# dtmf_rx.net
KiCad netlist of a schematic drawn in EAGLE
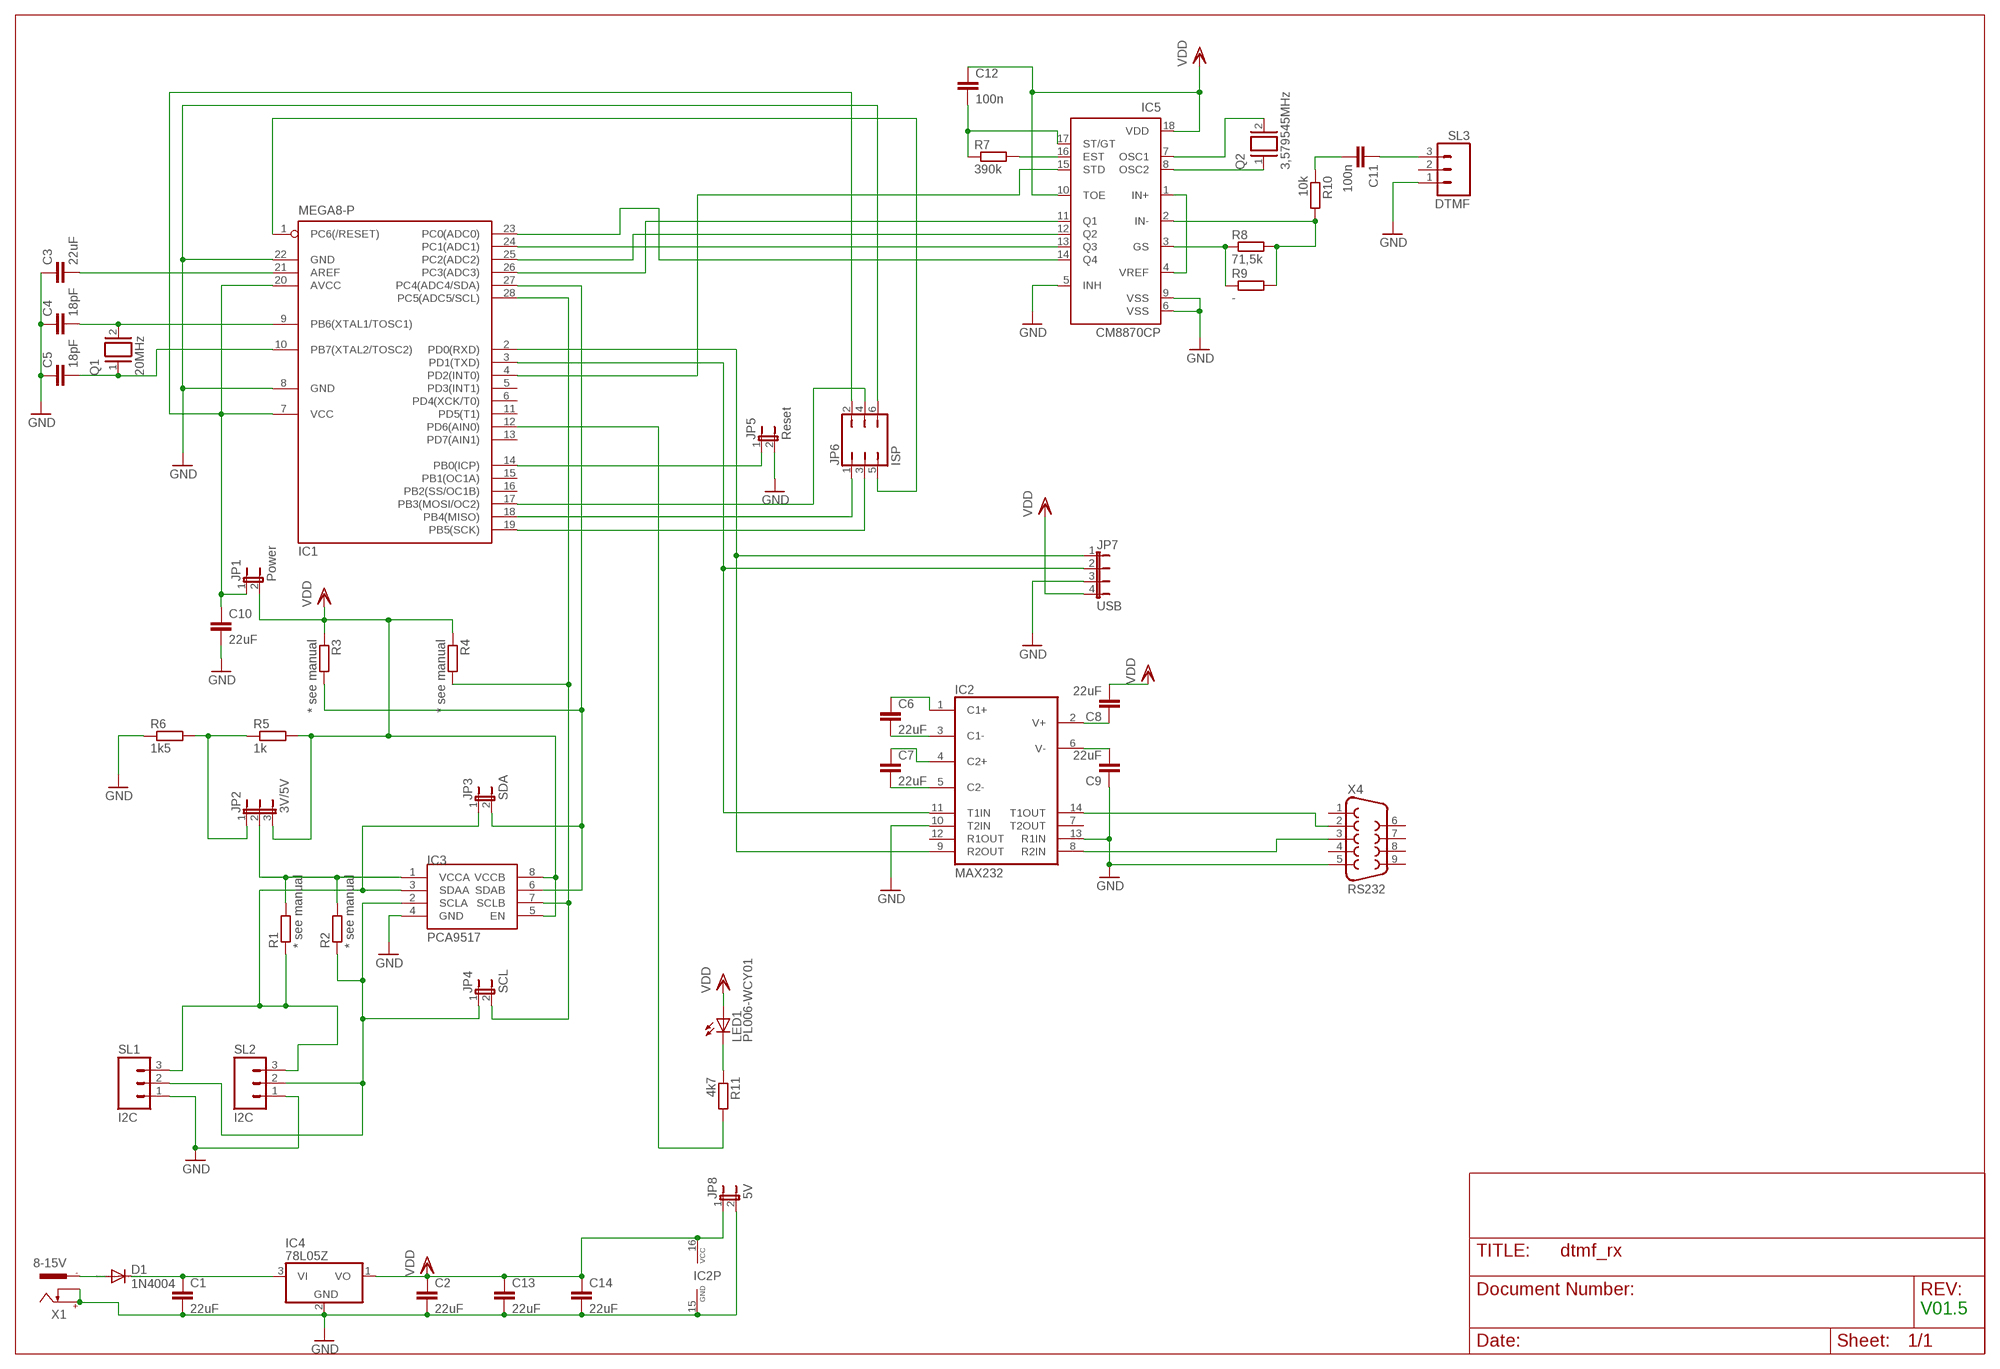
[diagram p0: schematic, sheet 1]

(export (version "E")
  (design (tool "Eeschema 10.0.6"))
  (components
    (comp (ref "C1")
      (value "22uF")
      (footprint "eagle-import:C1206")
      (libsource (lib "eagle-import") (part "C-EUC1206"))
    )
    (comp (ref "C2")
      (value "22uF")
      (footprint "eagle-import:C1206")
      (libsource (lib "eagle-import") (part "C-EUC1206"))
    )
    (comp (ref "C3")
      (value "22uF")
      (footprint "eagle-import:C1206")
      (libsource (lib "eagle-import") (part "C-EUC1206"))
    )
    (comp (ref "C4")
      (value "18pF")
      (footprint "eagle-import:C025-025X050")
      (libsource (lib "eagle-import") (part "resistor_C-EU025-025X050"))
    )
    (comp (ref "C5")
      (value "18pF")
      (footprint "eagle-import:C025-025X050")
      (libsource (lib "eagle-import") (part "resistor_C-EU025-025X050"))
    )
    (comp (ref "C6")
      (value "22uF")
      (footprint "eagle-import:C1206")
      (libsource (lib "eagle-import") (part "C-EUC1206"))
    )
    (comp (ref "C7")
      (value "22uF")
      (footprint "eagle-import:C1206")
      (libsource (lib "eagle-import") (part "C-EUC1206"))
    )
    (comp (ref "C8")
      (value "22uF")
      (footprint "eagle-import:C1206")
      (libsource (lib "eagle-import") (part "C-EUC1206"))
    )
    (comp (ref "C9")
      (value "22uF")
      (footprint "eagle-import:C1206")
      (libsource (lib "eagle-import") (part "C-EUC1206"))
    )
    (comp (ref "C10")
      (value "22uF")
      (footprint "eagle-import:C1206")
      (libsource (lib "eagle-import") (part "C-EUC1206"))
    )
    (comp (ref "C11")
      (value "100n")
      (footprint "eagle-import:C050-025X075")
      (libsource (lib "eagle-import") (part "C-EU050-025X075"))
    )
    (comp (ref "C12")
      (value "100n")
      (footprint "eagle-import:C050-025X075")
      (libsource (lib "eagle-import") (part "C-EU050-025X075"))
    )
    (comp (ref "C13")
      (value "22uF")
      (footprint "eagle-import:C1206")
      (libsource (lib "eagle-import") (part "C-EUC1206"))
    )
    (comp (ref "C14")
      (value "22uF")
      (footprint "eagle-import:C1206")
      (libsource (lib "eagle-import") (part "C-EUC1206"))
    )
    (comp (ref "D1")
      (value "1N4004")
      (footprint "eagle-import:DO41-10")
      (libsource (lib "eagle-import") (part "1N4004"))
    )
    (comp (ref "IC1")
      (value "MEGA8-P")
      (footprint "eagle-import:DIL28-3")
      (libsource (lib "eagle-import") (part "MEGA8-P"))
    )
    (comp (ref "IC2")
      (value "MAX232")
      (footprint "eagle-import:DIL16")
      (fields (field (name "MF") "MAXIM") (field (name "MPN") "MAX232ACPE+"))
      (libsource (lib "eagle-import") (part "MAX232"))
    )
    (comp (ref "IC3")
      (value "PCA9517")
      (footprint "eagle-import:SO-08")
      (libsource (lib "eagle-import") (part "PCA9517"))
    )
    (comp (ref "IC4")
      (value "78L05Z")
      (footprint "eagle-import:TO92")
      (libsource (lib "eagle-import") (part "78ZL05"))
    )
    (comp (ref "IC5")
      (value "CM8870CP")
      (footprint "eagle-import:DIL18")
      (libsource (lib "eagle-import") (part "CM8870CP"))
    )
    (comp (ref "JP1")
      (value "Power")
      (footprint "eagle-import:JP1")
      (libsource (lib "eagle-import") (part "JP1E"))
    )
    (comp (ref "JP2")
      (value "3V/5V")
      (footprint "eagle-import:JP2")
      (libsource (lib "eagle-import") (part "JP2E"))
    )
    (comp (ref "JP3")
      (value "SDA")
      (footprint "eagle-import:JP1")
      (libsource (lib "eagle-import") (part "JP1E"))
    )
    (comp (ref "JP4")
      (value "SCL")
      (footprint "eagle-import:JP1")
      (libsource (lib "eagle-import") (part "JP1E"))
    )
    (comp (ref "JP5")
      (value "Reset")
      (footprint "eagle-import:JP1")
      (libsource (lib "eagle-import") (part "JP1E"))
    )
    (comp (ref "JP6")
      (value "ISP")
      (footprint "eagle-import:JP3Q")
      (libsource (lib "eagle-import") (part "JP3Q"))
    )
    (comp (ref "JP7")
      (value "USB")
      (footprint "eagle-import:JP4")
      (libsource (lib "eagle-import") (part "JP4E"))
    )
    (comp (ref "JP8")
      (value "5V")
      (footprint "eagle-import:JP1")
      (libsource (lib "eagle-import") (part "JP1E"))
    )
    (comp (ref "LED1")
      (value "PL006-WCY01")
      (footprint "eagle-import:SOT23")
      (libsource (lib "eagle-import") (part "PL006-WCY01"))
    )
    (comp (ref "Q1")
      (value "20MHz")
      (footprint "eagle-import:QS")
      (libsource (lib "eagle-import") (part "XTAL/S"))
    )
    (comp (ref "Q2")
      (value "3,579545MHz")
      (footprint "eagle-import:QS")
      (libsource (lib "eagle-import") (part "XTAL/S"))
    )
    (comp (ref "R1")
      (value "* see manual")
      (footprint "eagle-import:R1206")
      (libsource (lib "eagle-import") (part "R-EU_R1206"))
    )
    (comp (ref "R2")
      (value "* see manual")
      (footprint "eagle-import:R1206")
      (libsource (lib "eagle-import") (part "R-EU_R1206"))
    )
    (comp (ref "R3")
      (value "* see manual")
      (footprint "eagle-import:R1206")
      (libsource (lib "eagle-import") (part "R-EU_R1206"))
    )
    (comp (ref "R4")
      (value "* see manual")
      (footprint "eagle-import:R1206")
      (libsource (lib "eagle-import") (part "R-EU_R1206"))
    )
    (comp (ref "R5")
      (value "1k")
      (footprint "eagle-import:R1206")
      (libsource (lib "eagle-import") (part "R-EU_R1206"))
    )
    (comp (ref "R6")
      (value "1k5")
      (footprint "eagle-import:R1206")
      (libsource (lib "eagle-import") (part "R-EU_R1206"))
    )
    (comp (ref "R7")
      (value "390k")
      (footprint "eagle-import:R1206")
      (libsource (lib "eagle-import") (part "R-EU_R1206"))
    )
    (comp (ref "R8")
      (value "71,5k")
      (footprint "eagle-import:R1206")
      (libsource (lib "eagle-import") (part "R-EU_R1206"))
    )
    (comp (ref "R9")
      (value "-")
      (footprint "eagle-import:R1206")
      (libsource (lib "eagle-import") (part "R-EU_R1206"))
    )
    (comp (ref "R10")
      (value "10k")
      (footprint "eagle-import:R1206")
      (libsource (lib "eagle-import") (part "R-EU_R1206"))
    )
    (comp (ref "R11")
      (value "4k7")
      (footprint "eagle-import:R1206")
      (libsource (lib "eagle-import") (part "R-EU_R1206"))
    )
    (comp (ref "SL1")
      (value "I2C")
      (footprint "eagle-import:03P")
      (libsource (lib "eagle-import") (part "M03"))
    )
    (comp (ref "SL2")
      (value "I2C")
      (footprint "eagle-import:03P")
      (libsource (lib "eagle-import") (part "M03"))
    )
    (comp (ref "SL3")
      (value "DTMF")
      (footprint "eagle-import:03P")
      (libsource (lib "eagle-import") (part "M03"))
    )
    (comp (ref "X1")
      (value "8-15V")
      (footprint "eagle-import:737992-5")
      (libsource (lib "eagle-import") (part "737992-55"))
    )
    (comp (ref "X4")
      (value "RS232")
      (footprint "eagle-import:F09H")
      (libsource (lib "eagle-import") (part "F09H"))
    )
  )
  (nets
    (net (code "1") (name "GND") (class "Default")
      (node (ref "C1") (pin "2") (pinfunction "2_2") (pintype "passive"))
      (node (ref "C10") (pin "2") (pinfunction "2_2") (pintype "passive"))
      (node (ref "C13") (pin "2") (pinfunction "2_2") (pintype "passive"))
      (node (ref "C14") (pin "2") (pinfunction "2_2") (pintype "passive"))
      (node (ref "C2") (pin "2") (pinfunction "2_2") (pintype "passive"))
      (node (ref "C3") (pin "1") (pinfunction "1_1") (pintype "passive"))
      (node (ref "C4") (pin "1") (pinfunction "1_1") (pintype "passive"))
      (node (ref "C5") (pin "1") (pinfunction "1_1") (pintype "passive"))
      (node (ref "C9") (pin "1") (pinfunction "1_1") (pintype "passive"))
      (node (ref "IC1") (pin "22") (pinfunction "GND_22") (pintype "power_in"))
      (node (ref "IC1") (pin "8") (pinfunction "GND_8") (pintype "power_in"))
      (node (ref "IC2") (pin "10") (pinfunction "T2IN_10") (pintype "input"))
      (node (ref "IC2") (pin "13") (pinfunction "R1IN_13") (pintype "input"))
      (node (ref "IC2") (pin "15") (pinfunction "GND_15") (pintype "power_in"))
      (node (ref "IC3") (pin "4") (pinfunction "GND_4") (pintype "bidirectional"))
      (node (ref "IC4") (pin "2") (pinfunction "GND_2") (pintype "passive"))
      (node (ref "IC5") (pin "5") (pinfunction "INH_5") (pintype "input"))
      (node (ref "IC5") (pin "6") (pinfunction "VSS_6") (pintype "power_in"))
      (node (ref "IC5") (pin "9") (pinfunction "VSS_9") (pintype "power_in"))
      (node (ref "JP5") (pin "2") (pinfunction "2_2") (pintype "passive"))
      (node (ref "JP6") (pin "6") (pinfunction "6_6") (pintype "passive"))
      (node (ref "JP7") (pin "3") (pinfunction "3_3") (pintype "passive"))
      (node (ref "JP8") (pin "2") (pinfunction "2_2") (pintype "passive"))
      (node (ref "R6") (pin "1") (pinfunction "1_1") (pintype "passive"))
      (node (ref "SL1") (pin "1") (pinfunction "1_1") (pintype "passive"))
      (node (ref "SL2") (pin "1") (pinfunction "1_1") (pintype "passive"))
      (node (ref "SL3") (pin "1") (pinfunction "1_1") (pintype "passive"))
      (node (ref "X1") (pin "+") (pinfunction "+_+") (pintype "passive"))
      (node (ref "X1") (pin "K") (pinfunction "K_K") (pintype "passive"))
      (node (ref "X4") (pin "5") (pinfunction "5_5") (pintype "passive"))
    )
    (net (code "2") (name "Net-(C11-Pad1)") (class "Default")
      (node (ref "C11") (pin "1") (pinfunction "1_1") (pintype "passive"))
      (node (ref "SL3") (pin "3") (pinfunction "3_3") (pintype "passive"))
    )
    (net (code "3") (name "Net-(C11-Pad2)") (class "Default")
      (node (ref "C11") (pin "2") (pinfunction "2_2") (pintype "passive"))
      (node (ref "R10") (pin "1") (pinfunction "1_1") (pintype "passive"))
    )
    (net (code "4") (name "Net-(D1-PadA)") (class "Default")
      (node (ref "D1") (pin "A") (pinfunction "A_A") (pintype "passive"))
      (node (ref "X1") (pin "-1") (pinfunction "-1_-1") (pintype "passive"))
    )
    (net (code "5") (name "Net-(IC1-AREF)") (class "Default")
      (node (ref "C3") (pin "2") (pinfunction "2_2") (pintype "passive"))
      (node (ref "IC1") (pin "21") (pinfunction "AREF_21") (pintype "passive"))
    )
    (net (code "6") (name "Net-(IC1-AVCC)") (class "Default")
      (node (ref "C10") (pin "1") (pinfunction "1_1") (pintype "passive"))
      (node (ref "IC1") (pin "20") (pinfunction "AVCC_20") (pintype "power_in"))
      (node (ref "IC1") (pin "7") (pinfunction "VCC_7") (pintype "power_in"))
      (node (ref "JP1") (pin "1") (pinfunction "1_1") (pintype "passive"))
      (node (ref "JP6") (pin "2") (pinfunction "2_2") (pintype "passive"))
    )
    (net (code "7") (name "Net-(IC1-PB0(ICP))") (class "Default")
      (node (ref "IC1") (pin "14") (pinfunction "PB0(ICP)_14") (pintype "bidirectional"))
      (node (ref "JP5") (pin "1") (pinfunction "1_1") (pintype "passive"))
    )
    (net (code "8") (name "Net-(IC1-PB3(MOSI{slash}OC2))") (class "Default")
      (node (ref "IC1") (pin "17") (pinfunction "PB3(MOSI/OC2)_17") (pintype "bidirectional"))
      (node (ref "JP6") (pin "4") (pinfunction "4_4") (pintype "passive"))
    )
    (net (code "9") (name "Net-(IC1-PB4(MISO))") (class "Default")
      (node (ref "IC1") (pin "18") (pinfunction "PB4(MISO)_18") (pintype "bidirectional"))
      (node (ref "JP6") (pin "1") (pinfunction "1_1") (pintype "passive"))
    )
    (net (code "10") (name "Net-(IC1-PB5(SCK))") (class "Default")
      (node (ref "IC1") (pin "19") (pinfunction "PB5(SCK)_19") (pintype "bidirectional"))
      (node (ref "JP6") (pin "3") (pinfunction "3_3") (pintype "passive"))
    )
    (net (code "11") (name "Net-(IC1-PB6(XTAL1{slash}TOSC1))") (class "Default")
      (node (ref "C4") (pin "2") (pinfunction "2_2") (pintype "passive"))
      (node (ref "IC1") (pin "9") (pinfunction "PB6(XTAL1/TOSC1)_9") (pintype "bidirectional"))
      (node (ref "Q1") (pin "2") (pinfunction "2_2") (pintype "passive"))
    )
    (net (code "12") (name "Net-(IC1-PB7(XTAL2{slash}TOSC2))") (class "Default")
      (node (ref "C5") (pin "2") (pinfunction "2_2") (pintype "passive"))
      (node (ref "IC1") (pin "10") (pinfunction "PB7(XTAL2/TOSC2)_10") (pintype "bidirectional"))
      (node (ref "Q1") (pin "1") (pinfunction "1_1") (pintype "passive"))
    )
    (net (code "13") (name "Net-(IC1-PC0(ADC0))") (class "Default")
      (node (ref "IC1") (pin "23") (pinfunction "PC0(ADC0)_23") (pintype "bidirectional"))
      (node (ref "IC5") (pin "14") (pinfunction "Q4_14") (pintype "output"))
    )
    (net (code "14") (name "Net-(IC1-PC1(ADC1))") (class "Default")
      (node (ref "IC1") (pin "24") (pinfunction "PC1(ADC1)_24") (pintype "bidirectional"))
      (node (ref "IC5") (pin "13") (pinfunction "Q3_13") (pintype "output"))
    )
    (net (code "15") (name "Net-(IC1-PC2(ADC2))") (class "Default")
      (node (ref "IC1") (pin "25") (pinfunction "PC2(ADC2)_25") (pintype "bidirectional"))
      (node (ref "IC5") (pin "12") (pinfunction "Q2_12") (pintype "output"))
    )
    (net (code "16") (name "Net-(IC1-PC3(ADC3))") (class "Default")
      (node (ref "IC1") (pin "26") (pinfunction "PC3(ADC3)_26") (pintype "bidirectional"))
      (node (ref "IC5") (pin "11") (pinfunction "Q1_11") (pintype "output"))
    )
    (net (code "17") (name "Net-(IC1-PC4(ADC4{slash}SDA))") (class "Default")
      (node (ref "IC1") (pin "27") (pinfunction "PC4(ADC4/SDA)_27") (pintype "bidirectional"))
      (node (ref "IC3") (pin "6") (pinfunction "SDAB_6") (pintype "bidirectional"))
      (node (ref "JP3") (pin "2") (pinfunction "2_2") (pintype "passive"))
      (node (ref "R3") (pin "2") (pinfunction "2_2") (pintype "passive"))
    )
    (net (code "18") (name "Net-(IC1-PC5(ADC5{slash}SCL))") (class "Default")
      (node (ref "IC1") (pin "28") (pinfunction "PC5(ADC5/SCL)_28") (pintype "bidirectional"))
      (node (ref "IC3") (pin "7") (pinfunction "SCLB_7") (pintype "bidirectional"))
      (node (ref "JP4") (pin "2") (pinfunction "2_2") (pintype "passive"))
      (node (ref "R4") (pin "2") (pinfunction "2_2") (pintype "passive"))
    )
    (net (code "19") (name "Net-(IC1-PC6({slash}RESET))") (class "Default")
      (node (ref "IC1") (pin "1") (pinfunction "PC6(/RESET)_1") (pintype "bidirectional"))
      (node (ref "JP6") (pin "5") (pinfunction "5_5") (pintype "passive"))
    )
    (net (code "20") (name "Net-(IC1-PD0(RXD))") (class "Default")
      (node (ref "IC1") (pin "2") (pinfunction "PD0(RXD)_2") (pintype "bidirectional"))
      (node (ref "IC2") (pin "9") (pinfunction "R2OUT_9") (pintype "output"))
      (node (ref "JP7") (pin "1") (pinfunction "1_1") (pintype "passive"))
    )
    (net (code "21") (name "Net-(IC1-PD1(TXD))") (class "Default")
      (node (ref "IC1") (pin "3") (pinfunction "PD1(TXD)_3") (pintype "bidirectional"))
      (node (ref "IC2") (pin "11") (pinfunction "T1IN_11") (pintype "input"))
      (node (ref "JP7") (pin "2") (pinfunction "2_2") (pintype "passive"))
    )
    (net (code "22") (name "Net-(IC1-PD2(INT0))") (class "Default")
      (node (ref "IC1") (pin "4") (pinfunction "PD2(INT0)_4") (pintype "bidirectional"))
      (node (ref "IC5") (pin "15") (pinfunction "STD_15") (pintype "input"))
    )
    (net (code "23") (name "Net-(IC1-PD6(AIN0))") (class "Default")
      (node (ref "IC1") (pin "12") (pinfunction "PD6(AIN0)_12") (pintype "bidirectional"))
      (node (ref "R11") (pin "2") (pinfunction "2_2") (pintype "passive"))
    )
    (net (code "24") (name "Net-(IC2A-C1+)") (class "Default")
      (node (ref "C6") (pin "1") (pinfunction "1_1") (pintype "passive"))
      (node (ref "IC2") (pin "1") (pinfunction "C1+_1") (pintype "bidirectional"))
    )
    (net (code "25") (name "Net-(IC2A-C1-)") (class "Default")
      (node (ref "C6") (pin "2") (pinfunction "2_2") (pintype "passive"))
      (node (ref "IC2") (pin "3") (pinfunction "C1-_3") (pintype "bidirectional"))
    )
    (net (code "26") (name "Net-(IC2A-C2+)") (class "Default")
      (node (ref "C7") (pin "1") (pinfunction "1_1") (pintype "passive"))
      (node (ref "IC2") (pin "4") (pinfunction "C2+_4") (pintype "bidirectional"))
    )
    (net (code "27") (name "Net-(IC2A-C2-)") (class "Default")
      (node (ref "C7") (pin "2") (pinfunction "2_2") (pintype "passive"))
      (node (ref "IC2") (pin "5") (pinfunction "C2-_5") (pintype "bidirectional"))
    )
    (net (code "28") (name "Net-(IC2A-R2IN)") (class "Default")
      (node (ref "IC2") (pin "8") (pinfunction "R2IN_8") (pintype "input"))
      (node (ref "X4") (pin "3") (pinfunction "3_3") (pintype "passive"))
    )
    (net (code "29") (name "Net-(IC2A-T1OUT)") (class "Default")
      (node (ref "IC2") (pin "14") (pinfunction "T1OUT_14") (pintype "output"))
      (node (ref "X4") (pin "2") (pinfunction "2_2") (pintype "passive"))
    )
    (net (code "30") (name "Net-(IC2A-V+)") (class "Default")
      (node (ref "C8") (pin "1") (pinfunction "1_1") (pintype "passive"))
      (node (ref "IC2") (pin "2") (pinfunction "V+_2") (pintype "bidirectional"))
    )
    (net (code "31") (name "Net-(IC2A-V-)") (class "Default")
      (node (ref "C9") (pin "2") (pinfunction "2_2") (pintype "passive"))
      (node (ref "IC2") (pin "6") (pinfunction "V-_6") (pintype "bidirectional"))
    )
    (net (code "32") (name "Net-(IC3-SCLA)") (class "Default")
      (node (ref "IC3") (pin "2") (pinfunction "SCLA_2") (pintype "bidirectional"))
      (node (ref "JP4") (pin "1") (pinfunction "1_1") (pintype "passive"))
      (node (ref "R2") (pin "1") (pinfunction "1_1") (pintype "passive"))
      (node (ref "SL1") (pin "2") (pinfunction "2_2") (pintype "passive"))
      (node (ref "SL2") (pin "2") (pinfunction "2_2") (pintype "passive"))
    )
    (net (code "33") (name "Net-(IC3-SDAA)") (class "Default")
      (node (ref "IC3") (pin "3") (pinfunction "SDAA_3") (pintype "bidirectional"))
      (node (ref "JP3") (pin "1") (pinfunction "1_1") (pintype "passive"))
      (node (ref "R1") (pin "1") (pinfunction "1_1") (pintype "passive"))
      (node (ref "SL1") (pin "3") (pinfunction "3_3") (pintype "passive"))
      (node (ref "SL2") (pin "3") (pinfunction "3_3") (pintype "passive"))
    )
    (net (code "34") (name "Net-(IC3-VCCA)") (class "Default")
      (node (ref "IC3") (pin "1") (pinfunction "VCCA_1") (pintype "bidirectional"))
      (node (ref "JP2") (pin "2") (pinfunction "2_2") (pintype "passive"))
      (node (ref "R1") (pin "2") (pinfunction "2_2") (pintype "passive"))
      (node (ref "R2") (pin "2") (pinfunction "2_2") (pintype "passive"))
    )
    (net (code "35") (name "Net-(IC4-VI)") (class "Default")
      (node (ref "C1") (pin "1") (pinfunction "1_1") (pintype "passive"))
      (node (ref "D1") (pin "C") (pinfunction "C_C") (pintype "passive"))
      (node (ref "IC4") (pin "3") (pinfunction "VI_3") (pintype "input"))
    )
    (net (code "36") (name "Net-(IC5-EST)") (class "Default")
      (node (ref "IC5") (pin "16") (pinfunction "EST_16") (pintype "input"))
      (node (ref "R7") (pin "2") (pinfunction "2_2") (pintype "passive"))
    )
    (net (code "37") (name "Net-(IC5-GS)") (class "Default")
      (node (ref "IC5") (pin "3") (pinfunction "GS_3") (pintype "input"))
      (node (ref "R8") (pin "1") (pinfunction "1_1") (pintype "passive"))
      (node (ref "R9") (pin "1") (pinfunction "1_1") (pintype "passive"))
    )
    (net (code "38") (name "Net-(IC5-IN+)") (class "Default")
      (node (ref "IC5") (pin "1") (pinfunction "IN+_1") (pintype "input"))
      (node (ref "IC5") (pin "4") (pinfunction "VREF_4") (pintype "output"))
    )
    (net (code "39") (name "Net-(IC5-IN-)") (class "Default")
      (node (ref "IC5") (pin "2") (pinfunction "IN-_2") (pintype "input"))
      (node (ref "R10") (pin "2") (pinfunction "2_2") (pintype "passive"))
      (node (ref "R8") (pin "2") (pinfunction "2_2") (pintype "passive"))
      (node (ref "R9") (pin "2") (pinfunction "2_2") (pintype "passive"))
    )
    (net (code "40") (name "Net-(IC5-OSC1)") (class "Default")
      (node (ref "IC5") (pin "7") (pinfunction "OSC1_7") (pintype "input"))
      (node (ref "Q2") (pin "2") (pinfunction "2_2") (pintype "passive"))
    )
    (net (code "41") (name "Net-(IC5-OSC2)") (class "Default")
      (node (ref "IC5") (pin "8") (pinfunction "OSC2_8") (pintype "bidirectional"))
      (node (ref "Q2") (pin "1") (pinfunction "1_1") (pintype "passive"))
    )
    (net (code "42") (name "Net-(IC5-ST{slash}GT)") (class "Default")
      (node (ref "C12") (pin "2") (pinfunction "2_2") (pintype "passive"))
      (node (ref "IC5") (pin "17") (pinfunction "ST/GT_17") (pintype "bidirectional"))
      (node (ref "R7") (pin "1") (pinfunction "1_1") (pintype "passive"))
    )
    (net (code "43") (name "Net-(JP2-Pad1)") (class "Default")
      (node (ref "JP2") (pin "1") (pinfunction "1_1") (pintype "passive"))
      (node (ref "R5") (pin "1") (pinfunction "1_1") (pintype "passive"))
      (node (ref "R6") (pin "2") (pinfunction "2_2") (pintype "passive"))
    )
    (net (code "44") (name "Net-(LED1-C)") (class "Default")
      (node (ref "LED1") (pin "3") (pinfunction "C_3") (pintype "passive"))
      (node (ref "R11") (pin "1") (pinfunction "1_1") (pintype "passive"))
    )
    (net (code "45") (name "VDD") (class "Default")
      (node (ref "C12") (pin "1") (pinfunction "1_1") (pintype "passive"))
      (node (ref "C13") (pin "1") (pinfunction "1_1") (pintype "passive"))
      (node (ref "C14") (pin "1") (pinfunction "1_1") (pintype "passive"))
      (node (ref "C2") (pin "1") (pinfunction "1_1") (pintype "passive"))
      (node (ref "C8") (pin "2") (pinfunction "2_2") (pintype "passive"))
      (node (ref "IC2") (pin "16") (pinfunction "VCC_16") (pintype "power_in"))
      (node (ref "IC3") (pin "5") (pinfunction "EN_5") (pintype "bidirectional"))
      (node (ref "IC3") (pin "8") (pinfunction "VCCB_8") (pintype "bidirectional"))
      (node (ref "IC4") (pin "1") (pinfunction "VO_1") (pintype "passive"))
      (node (ref "IC5") (pin "10") (pinfunction "TOE_10") (pintype "input"))
      (node (ref "IC5") (pin "18") (pinfunction "VDD_18") (pintype "power_in"))
      (node (ref "JP1") (pin "2") (pinfunction "2_2") (pintype "passive"))
      (node (ref "JP2") (pin "3") (pinfunction "3_3") (pintype "passive"))
      (node (ref "JP7") (pin "4") (pinfunction "4_4") (pintype "passive"))
      (node (ref "JP8") (pin "1") (pinfunction "1_1") (pintype "passive"))
      (node (ref "LED1") (pin "1") (pinfunction "A_1") (pintype "passive"))
      (node (ref "R3") (pin "1") (pinfunction "1_1") (pintype "passive"))
      (node (ref "R4") (pin "1") (pinfunction "1_1") (pintype "passive"))
      (node (ref "R5") (pin "2") (pinfunction "2_2") (pintype "passive"))
    )
    (net (code "46") (name "unconnected-(IC1-PB1(OC1A)-Pad15)") (class "Default")
      (node (ref "IC1") (pin "15") (pinfunction "PB1(OC1A)_15") (pintype "bidirectional"))
    )
    (net (code "47") (name "unconnected-(IC1-PB2(SS{slash}OC1B)-Pad16)") (class "Default")
      (node (ref "IC1") (pin "16") (pinfunction "PB2(SS/OC1B)_16") (pintype "bidirectional"))
    )
    (net (code "48") (name "unconnected-(IC1-PD3(INT1)-Pad5)") (class "Default")
      (node (ref "IC1") (pin "5") (pinfunction "PD3(INT1)_5") (pintype "bidirectional"))
    )
    (net (code "49") (name "unconnected-(IC1-PD4(XCK{slash}T0)-Pad6)") (class "Default")
      (node (ref "IC1") (pin "6") (pinfunction "PD4(XCK/T0)_6") (pintype "bidirectional"))
    )
    (net (code "50") (name "unconnected-(IC1-PD5(T1)-Pad11)") (class "Default")
      (node (ref "IC1") (pin "11") (pinfunction "PD5(T1)_11") (pintype "bidirectional"))
    )
    (net (code "51") (name "unconnected-(IC1-PD7(AIN1)-Pad13)") (class "Default")
      (node (ref "IC1") (pin "13") (pinfunction "PD7(AIN1)_13") (pintype "bidirectional"))
    )
    (net (code "52") (name "unconnected-(IC2A-R1OUT-Pad12)") (class "Default")
      (node (ref "IC2") (pin "12") (pinfunction "R1OUT_12") (pintype "output"))
    )
    (net (code "53") (name "unconnected-(IC2A-T2OUT-Pad7)") (class "Default")
      (node (ref "IC2") (pin "7") (pinfunction "T2OUT_7") (pintype "output"))
    )
    (net (code "54") (name "unconnected-(SL3-Pad2)") (class "Default")
      (node (ref "SL3") (pin "2") (pinfunction "2_2") (pintype "passive"))
    )
    (net (code "55") (name "unconnected-(X1-Pad-2)") (class "Default")
      (node (ref "X1") (pin "-2") (pinfunction "-2_-2") (pintype "passive"))
    )
    (net (code "56") (name "unconnected-(X4-Pad1)") (class "Default")
      (node (ref "X4") (pin "1") (pinfunction "1_1") (pintype "passive"))
    )
    (net (code "57") (name "unconnected-(X4-Pad4)") (class "Default")
      (node (ref "X4") (pin "4") (pinfunction "4_4") (pintype "passive"))
    )
    (net (code "58") (name "unconnected-(X4-Pad6)") (class "Default")
      (node (ref "X4") (pin "6") (pinfunction "6_6") (pintype "passive"))
    )
    (net (code "59") (name "unconnected-(X4-Pad7)") (class "Default")
      (node (ref "X4") (pin "7") (pinfunction "7_7") (pintype "passive"))
    )
    (net (code "60") (name "unconnected-(X4-Pad8)") (class "Default")
      (node (ref "X4") (pin "8") (pinfunction "8_8") (pintype "passive"))
    )
    (net (code "61") (name "unconnected-(X4-Pad9)") (class "Default")
      (node (ref "X4") (pin "9") (pinfunction "9_9") (pintype "passive"))
    )
  )
)
